# caps-lock-buzzer.net
KiCad netlist of a schematic drawn in EAGLE
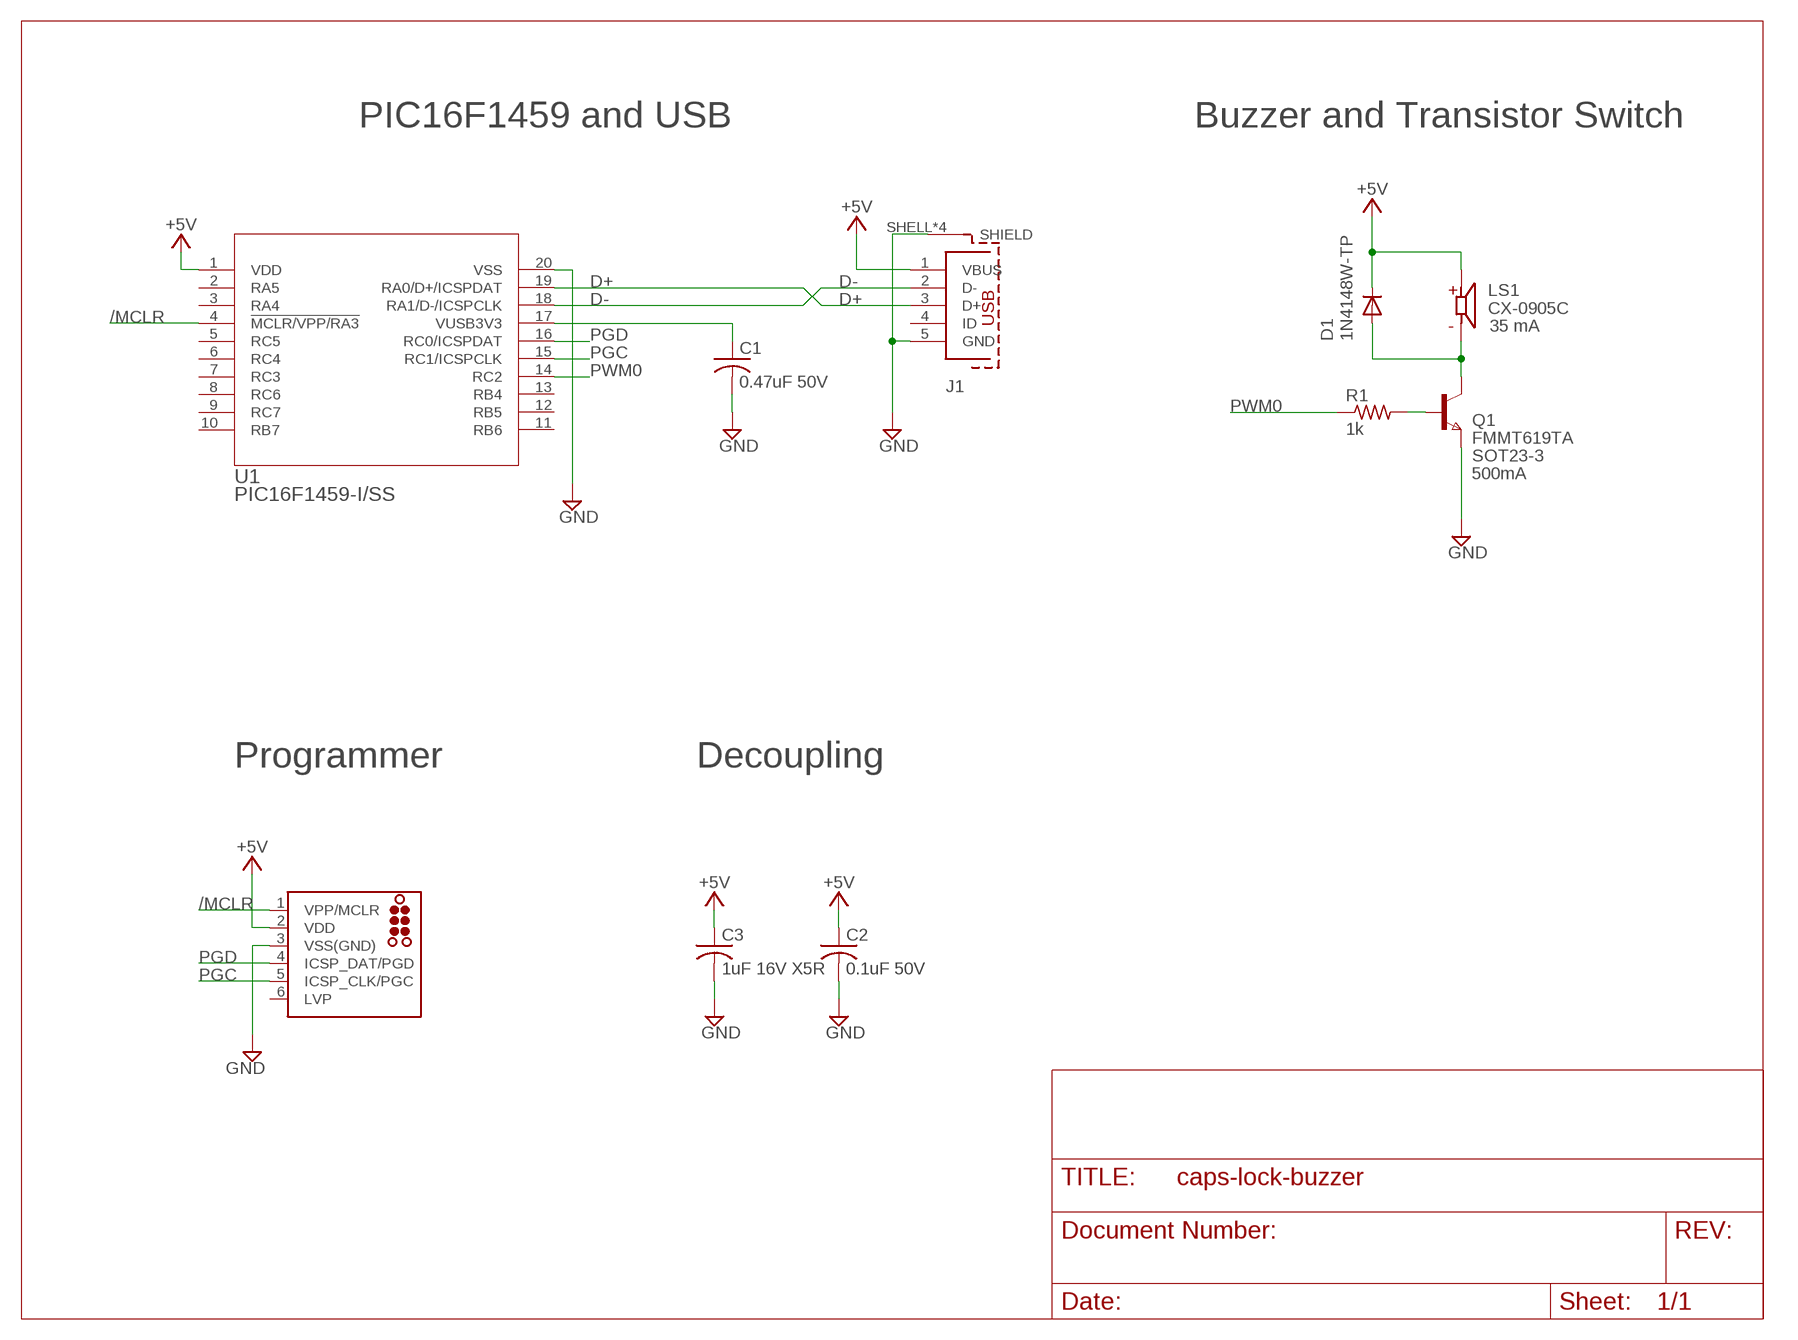
[diagram p0: schematic, sheet 1]

(export (version "E")
  (design (tool "Eeschema 10.0.6"))
  (components
    (comp (ref "C1")
      (value "0.47uF 50V")
      (footprint "eagle-import:C1206K")
      (fields (field (name "MFR") "KEMET") (field (name "MFR_PART_NO") "C1206C474K5RACTU"))
      (libsource (lib "eagle-import") (part "C-USC1206K"))
    )
    (comp (ref "C2")
      (value "0.1uF 50V")
      (footprint "eagle-import:C1206K")
      (fields (field (name "MFR") "KEMET") (field (name "MFR_PART_NO") "C1206S104M5RACTU"))
      (libsource (lib "eagle-import") (part "C-USC1206K"))
    )
    (comp (ref "C3")
      (value "1uF 16V X5R")
      (footprint "eagle-import:C1210")
      (fields (field (name "MFR") "KEMET") (field (name "MFR_PART_NO") "C1210C105K4PACTU"))
      (libsource (lib "eagle-import") (part "C-USC1210"))
    )
    (comp (ref "D1")
      (value "1N4148W-TP")
      (footprint "eagle-import:SOD123")
      (libsource (lib "eagle-import") (part "DIODE-SOD123"))
    )
    (comp (ref "J1")
      (value "629105136821")
      (footprint "eagle-import:629105136821")
      (libsource (lib "eagle-import") (part "629105136821"))
    )
    (comp (ref "J3")
      (value "TC2030-MCP-NL")
      (footprint "eagle-import:TC2030-MCP-NL")
      (libsource (lib "eagle-import") (part "TC2030-MCP-NL"))
    )
    (comp (ref "LS1")
      (value "CX-0905C")
      (footprint "eagle-import:CUI_CX-0905C")
      (fields (field (name "MF") "CUI"))
      (libsource (lib "eagle-import") (part "CX-0905C"))
    )
    (comp (ref "Q1")
      (value "FMMT619TA")
      (footprint "eagle-import:SOT-23")
      (fields (field (name "MPN") "DSS20201L-7"))
      (libsource (lib "eagle-import") (part "NPNSOT23"))
    )
    (comp (ref "R1")
      (value "1k")
      (footprint "eagle-import:R0805")
      (libsource (lib "eagle-import") (part "R-US_R0805"))
    )
    (comp (ref "U1")
      (value "PIC16F1459-I/SS")
      (footprint "eagle-import:SSOP20_MC")
      (fields (field (name "MANUFACTURER_PART_NUMBER") "PIC16F1459ISS"))
      (libsource (lib "eagle-import") (part "PIC16F1459-I/SS"))
    )
  )
  (nets
    (net (code "1") (name "+5V") (class "Default")
      (node (ref "C2") (pin "1") (pinfunction "1_1") (pintype "passive"))
      (node (ref "C3") (pin "1") (pinfunction "1_1") (pintype "passive"))
      (node (ref "D1") (pin "C") (pinfunction "C_C") (pintype "passive"))
      (node (ref "J1") (pin "1") (pinfunction "VBUS_1") (pintype "passive"))
      (node (ref "J3") (pin "2") (pinfunction "VDD_2") (pintype "power_in"))
      (node (ref "LS1") (pin "P") (pinfunction "P_P") (pintype "passive"))
      (node (ref "U1") (pin "1") (pinfunction "VDD_1") (pintype "power_in"))
    )
    (net (code "2") (name "/D+") (class "Default")
      (node (ref "J1") (pin "3") (pinfunction "D+_3") (pintype "passive"))
      (node (ref "U1") (pin "19") (pinfunction "RA0/D+/ICSPDAT_19") (pintype "bidirectional"))
    )
    (net (code "3") (name "/D-") (class "Default")
      (node (ref "J1") (pin "2") (pinfunction "D-_2") (pintype "passive"))
      (node (ref "U1") (pin "18") (pinfunction "RA1/D-/ICSPCLK_18") (pintype "bidirectional"))
    )
    (net (code "4") (name "/PGC") (class "Default")
      (node (ref "J3") (pin "5") (pinfunction "ICSP_CLK/PGC_5") (pintype "output"))
      (node (ref "U1") (pin "15") (pinfunction "RC1/ICSPCLK_15") (pintype "bidirectional"))
    )
    (net (code "5") (name "/PGD") (class "Default")
      (node (ref "J3") (pin "4") (pinfunction "ICSP_DAT/PGD_4") (pintype "bidirectional"))
      (node (ref "U1") (pin "16") (pinfunction "RC0/ICSPDAT_16") (pintype "bidirectional"))
    )
    (net (code "6") (name "/PWM0") (class "Default")
      (node (ref "R1") (pin "1") (pinfunction "1_1") (pintype "passive"))
      (node (ref "U1") (pin "14") (pinfunction "RC2_14") (pintype "bidirectional"))
    )
    (net (code "7") (name "/{slash}MCLR") (class "Default")
      (node (ref "J3") (pin "1") (pinfunction "VPP/MCLR_1") (pintype "passive"))
      (node (ref "U1") (pin "4") (pinfunction "~{MCLR/VPP/RA3}_4") (pintype "bidirectional"))
    )
    (net (code "8") (name "GND") (class "Default")
      (node (ref "C1") (pin "2") (pinfunction "2_2") (pintype "passive"))
      (node (ref "C2") (pin "2") (pinfunction "2_2") (pintype "passive"))
      (node (ref "C3") (pin "2") (pinfunction "2_2") (pintype "passive"))
      (node (ref "J1") (pin "5") (pinfunction "GND_5") (pintype "passive"))
      (node (ref "J1") (pin "SHELL") (pinfunction "SHIELD_SHELL") (pintype "passive"))
      (node (ref "J1") (pin "SHELL1") (pinfunction "SHIELD_SHELL1") (pintype "passive"))
      (node (ref "J1") (pin "SHELL2") (pinfunction "SHIELD_SHELL2") (pintype "passive"))
      (node (ref "J1") (pin "SHELL3") (pinfunction "SHIELD_SHELL3") (pintype "passive"))
      (node (ref "J3") (pin "3") (pinfunction "VSS(GND)_3") (pintype "power_in"))
      (node (ref "Q1") (pin "2") (pinfunction "E_2") (pintype "passive"))
      (node (ref "U1") (pin "20") (pinfunction "VSS_20") (pintype "power_in"))
    )
    (net (code "9") (name "Net-(Q1-B)") (class "Default")
      (node (ref "Q1") (pin "3") (pinfunction "B_3") (pintype "passive"))
      (node (ref "R1") (pin "2") (pinfunction "2_2") (pintype "passive"))
    )
    (net (code "10") (name "Net-(Q1-C)") (class "Default")
      (node (ref "D1") (pin "A") (pinfunction "A_A") (pintype "passive"))
      (node (ref "LS1") (pin "N") (pinfunction "N_N") (pintype "passive"))
      (node (ref "Q1") (pin "1") (pinfunction "C_1") (pintype "passive"))
    )
    (net (code "11") (name "Net-(U1-VUSB3V3)") (class "Default")
      (node (ref "C1") (pin "1") (pinfunction "1_1") (pintype "passive"))
      (node (ref "U1") (pin "17") (pinfunction "VUSB3V3_17") (pintype "power_in"))
    )
    (net (code "12") (name "unconnected-(J1-ID-Pad4)") (class "Default")
      (node (ref "J1") (pin "4") (pinfunction "ID_4") (pintype "passive"))
    )
    (net (code "13") (name "unconnected-(J3-LVP-Pad6)") (class "Default")
      (node (ref "J3") (pin "6") (pinfunction "LVP_6") (pintype "bidirectional"))
    )
    (net (code "14") (name "unconnected-(U1-RA4-Pad3)") (class "Default")
      (node (ref "U1") (pin "3") (pinfunction "RA4_3") (pintype "bidirectional"))
    )
    (net (code "15") (name "unconnected-(U1-RA5-Pad2)") (class "Default")
      (node (ref "U1") (pin "2") (pinfunction "RA5_2") (pintype "bidirectional"))
    )
    (net (code "16") (name "unconnected-(U1-RB4-Pad13)") (class "Default")
      (node (ref "U1") (pin "13") (pinfunction "RB4_13") (pintype "bidirectional"))
    )
    (net (code "17") (name "unconnected-(U1-RB5-Pad12)") (class "Default")
      (node (ref "U1") (pin "12") (pinfunction "RB5_12") (pintype "bidirectional"))
    )
    (net (code "18") (name "unconnected-(U1-RB6-Pad11)") (class "Default")
      (node (ref "U1") (pin "11") (pinfunction "RB6_11") (pintype "bidirectional"))
    )
    (net (code "19") (name "unconnected-(U1-RB7-Pad10)") (class "Default")
      (node (ref "U1") (pin "10") (pinfunction "RB7_10") (pintype "bidirectional"))
    )
    (net (code "20") (name "unconnected-(U1-RC3-Pad7)") (class "Default")
      (node (ref "U1") (pin "7") (pinfunction "RC3_7") (pintype "bidirectional"))
    )
    (net (code "21") (name "unconnected-(U1-RC4-Pad6)") (class "Default")
      (node (ref "U1") (pin "6") (pinfunction "RC4_6") (pintype "bidirectional"))
    )
    (net (code "22") (name "unconnected-(U1-RC5-Pad5)") (class "Default")
      (node (ref "U1") (pin "5") (pinfunction "RC5_5") (pintype "bidirectional"))
    )
    (net (code "23") (name "unconnected-(U1-RC6-Pad8)") (class "Default")
      (node (ref "U1") (pin "8") (pinfunction "RC6_8") (pintype "bidirectional"))
    )
    (net (code "24") (name "unconnected-(U1-RC7-Pad9)") (class "Default")
      (node (ref "U1") (pin "9") (pinfunction "RC7_9") (pintype "bidirectional"))
    )
  )
)
